# WR_OSC.net
KiCad netlist of a schematic drawn in Altium Designer
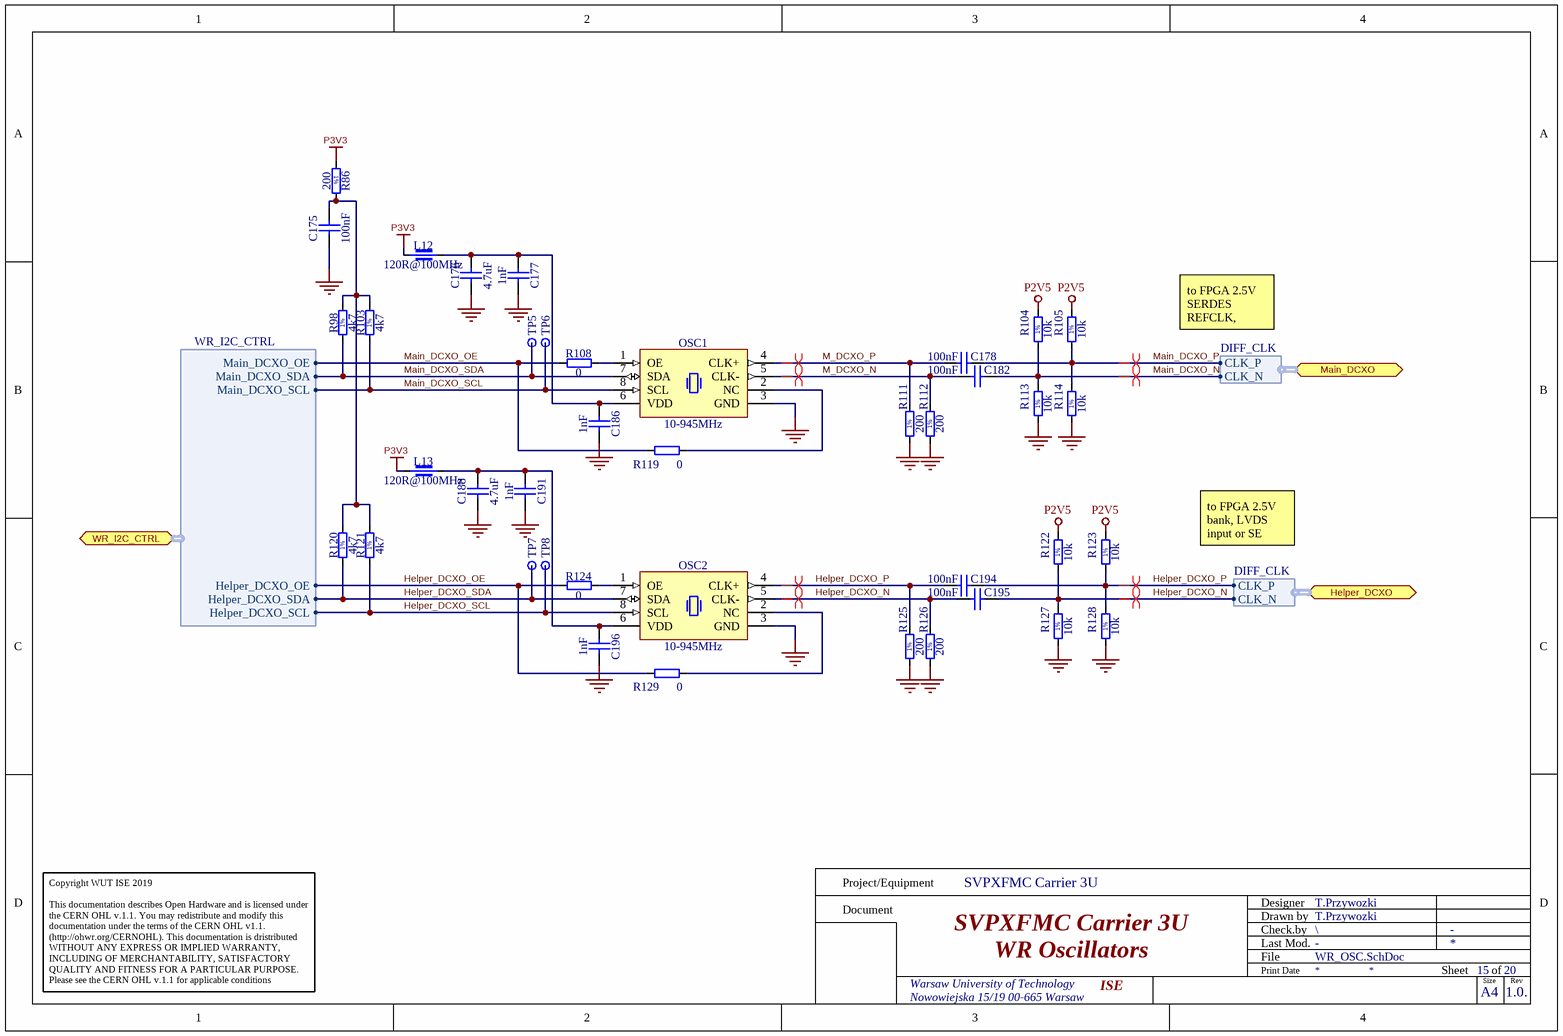
[diagram p0: WR_OSC.SchDoc]

(export (version "E")
  (design (tool "Eeschema 10.0.6"))
  (components
    (comp (ref "C175")
      (value "100nF")
      (footprint "CAPC0603X33N")
      (description "Non-polarised capacitor")
      (fields
        (field (name "MANUFACTURER PART NUMBER") "CC0201_100NF_6.3V_10%_X5R")
        (field (name "MANUFACTURER") "GENERIC")
        (field (name "AUTHOR") "CERN DEM JLC")
      )
      (libsource (lib "Capacitors") (part "Capacitor - non polarized"))
    )
    (comp (ref "C176")
      (value "4.7uF")
      (footprint "CAPC1608X90N")
      (description "Non-polarised capacitor")
      (fields
        (field (name "MANUFACTURER PART NUMBER") "CC0603_4.7UF_25V_10%_X5R")
        (field (name "MANUFACTURER") "GENERIC")
        (field (name "AUTHOR") "CERN DEM JLC")
      )
      (libsource (lib "Capacitors") (part "Capacitor - non polarized"))
    )
    (comp (ref "C177")
      (value "1nF")
      (footprint "CAPC0603X33N")
      (description "Non-polarised capacitor")
      (fields
        (field (name "MANUFACTURER PART NUMBER") "CC0201_1NF_16V_10%_X5R")
        (field (name "MANUFACTURER") "GENERIC")
        (field (name "AUTHOR") "CERN DEM JLC")
      )
      (libsource (lib "Capacitors") (part "Capacitor - non polarized"))
    )
    (comp (ref "C178")
      (value "100nF")
      (footprint "CAPC1005X55N")
      (description "Non-polarised capacitor")
      (fields
        (field (name "MANUFACTURER PART NUMBER") "CC0402_100NF_16V_10%_X5R")
        (field (name "MANUFACTURER") "GENERIC")
        (field (name "AUTHOR") "CERN DEM JLC")
      )
      (libsource (lib "Capacitors") (part "Capacitor - non polarized"))
    )
    (comp (ref "C182")
      (value "100nF")
      (footprint "CAPC1005X55N")
      (description "Non-polarised capacitor")
      (fields
        (field (name "MANUFACTURER PART NUMBER") "CC0402_100NF_16V_10%_X5R")
        (field (name "MANUFACTURER") "GENERIC")
        (field (name "AUTHOR") "CERN DEM JLC")
      )
      (libsource (lib "Capacitors") (part "Capacitor - non polarized"))
    )
    (comp (ref "C186")
      (value "1nF")
      (footprint "CAPC0603X33N")
      (description "Non-polarised capacitor")
      (fields
        (field (name "MANUFACTURER PART NUMBER") "CC0201_1NF_16V_10%_X5R")
        (field (name "MANUFACTURER") "GENERIC")
        (field (name "AUTHOR") "CERN DEM JLC")
      )
      (libsource (lib "Capacitors") (part "Capacitor - non polarized"))
    )
    (comp (ref "C188")
      (value "4.7uF")
      (footprint "CAPC1608X90N")
      (description "Non-polarised capacitor")
      (fields
        (field (name "MANUFACTURER PART NUMBER") "CC0603_4.7UF_25V_10%_X5R")
        (field (name "MANUFACTURER") "GENERIC")
        (field (name "AUTHOR") "CERN DEM JLC")
      )
      (libsource (lib "Capacitors") (part "Capacitor - non polarized"))
    )
    (comp (ref "C191")
      (value "1nF")
      (footprint "CAPC0603X33N")
      (description "Non-polarised capacitor")
      (fields
        (field (name "MANUFACTURER PART NUMBER") "CC0201_1NF_16V_10%_X5R")
        (field (name "MANUFACTURER") "GENERIC")
        (field (name "AUTHOR") "CERN DEM JLC")
      )
      (libsource (lib "Capacitors") (part "Capacitor - non polarized"))
    )
    (comp (ref "C194")
      (value "100nF")
      (footprint "CAPC1005X55N")
      (description "Non-polarised capacitor")
      (fields
        (field (name "MANUFACTURER PART NUMBER") "CC0402_100NF_16V_10%_X5R")
        (field (name "MANUFACTURER") "GENERIC")
        (field (name "AUTHOR") "CERN DEM JLC")
      )
      (libsource (lib "Capacitors") (part "Capacitor - non polarized"))
    )
    (comp (ref "C195")
      (value "100nF")
      (footprint "CAPC1005X55N")
      (description "Non-polarised capacitor")
      (fields
        (field (name "MANUFACTURER PART NUMBER") "CC0402_100NF_16V_10%_X5R")
        (field (name "MANUFACTURER") "GENERIC")
        (field (name "AUTHOR") "CERN DEM JLC")
      )
      (libsource (lib "Capacitors") (part "Capacitor - non polarized"))
    )
    (comp (ref "C196")
      (value "1nF")
      (footprint "CAPC0603X33N")
      (description "Non-polarised capacitor")
      (fields
        (field (name "MANUFACTURER PART NUMBER") "CC0201_1NF_16V_10%_X5R")
        (field (name "MANUFACTURER") "GENERIC")
        (field (name "AUTHOR") "CERN DEM JLC")
      )
      (libsource (lib "Capacitors") (part "Capacitor - non polarized"))
    )
    (comp (ref "L12")
      (value "120R@100MHz")
      (footprint "INDC1608X95N")
      (fields
        (field (name "MANUFACTURER PART NUMBER") "BLM18PG121SN1D")
        (field (name "MANUFACTURER") "MURATA")
        (field (name "PART NUMBER") "IND0603_MURATA_BLM18PG121SN1D")
        (field (name "AUTHOR") "CERN DEM BC")
      )
      (libsource (lib "Inductors & Transformers") (part "Ferrite Bead"))
    )
    (comp (ref "L13")
      (value "120R@100MHz")
      (footprint "INDC1608X95N")
      (fields
        (field (name "MANUFACTURER PART NUMBER") "BLM18PG121SN1D")
        (field (name "MANUFACTURER") "MURATA")
        (field (name "PART NUMBER") "IND0603_MURATA_BLM18PG121SN1D")
        (field (name "AUTHOR") "CERN DEM BC")
      )
      (libsource (lib "Inductors & Transformers") (part "Ferrite Bead"))
    )
    (comp (ref "OSC1")
      (value "10-945MHz")
      (footprint "OSC_SILICON-LAB_SI570")
      (description "Ultra Low Jitter I2C Programmable XO (95 fs), 0.2 to 250MHz")
      (fields
        (field (name "MANUFACTURER") "Silabs")
        (field (name "MANUFACTURER PART NUMBER") "570ACA001527DGR")
      )
      (libsource (lib "TP_LIB") (part "570ACA001527DGR"))
    )
    (comp (ref "OSC2")
      (value "10-945MHz")
      (footprint "OSC_SILICON-LAB_SI570")
      (description "Ultra Low Jitter I2C Programmable XO (95 fs), 0.2 to 250MHz")
      (fields
        (field (name "MANUFACTURER") "Silabs")
        (field (name "MANUFACTURER PART NUMBER") "570ACA001527DGR")
      )
      (libsource (lib "TP_LIB") (part "570ACA001527DGR"))
    )
    (comp (ref "R86")
      (value "200")
      (footprint "RESC1005X40N")
      (description "Resistor - 1%")
      (fields
        (field (name "MANUFACTURER PART NUMBER") "R0402_200R_1%_0.0625W_100PPM")
        (field (name "MANUFACTURER") "GENERIC")
        (field (name "AUTHOR") "CERN DEM JLC")
      )
      (libsource (lib "Resistors") (part "Resistor - 1%"))
    )
    (comp (ref "R98")
      (value "4k7")
      (footprint "RESC1005X40N")
      (description "Resistor - 1%")
      (fields
        (field (name "MANUFACTURER PART NUMBER") "R0402_4K7_1%_0.0625W_100PPM")
        (field (name "MANUFACTURER") "GENERIC")
        (field (name "AUTHOR") "CERN DEM JLC")
      )
      (libsource (lib "Resistors") (part "Resistor - 1%"))
    )
    (comp (ref "R103")
      (value "4k7")
      (footprint "RESC1005X40N")
      (description "Resistor - 1%")
      (fields
        (field (name "MANUFACTURER PART NUMBER") "R0402_4K7_1%_0.0625W_100PPM")
        (field (name "MANUFACTURER") "GENERIC")
        (field (name "AUTHOR") "CERN DEM JLC")
      )
      (libsource (lib "Resistors") (part "Resistor - 1%"))
    )
    (comp (ref "R104")
      (value "10k")
      (footprint "RESC1005X40N")
      (description "Resistor - 1%")
      (fields
        (field (name "MANUFACTURER PART NUMBER") "R0402_10K_1%_0.0625W_100PPM")
        (field (name "MANUFACTURER") "GENERIC")
        (field (name "AUTHOR") "CERN DEM JLC")
      )
      (libsource (lib "Resistors") (part "Resistor - 1%"))
    )
    (comp (ref "R105")
      (value "10k")
      (footprint "RESC1005X40N")
      (description "Resistor - 1%")
      (fields
        (field (name "MANUFACTURER PART NUMBER") "R0402_10K_1%_0.0625W_100PPM")
        (field (name "MANUFACTURER") "GENERIC")
        (field (name "AUTHOR") "CERN DEM JLC")
      )
      (libsource (lib "Resistors") (part "Resistor - 1%"))
    )
    (comp (ref "R108")
      (value "0")
      (footprint "RESC1005X40N")
      (description "Resistor")
      (fields
        (field (name "MANUFACTURER PART NUMBER") "R0402_0R_JUMPER")
        (field (name "MANUFACTURER") "GENERIC")
        (field (name "AUTHOR") "CERN DEM JLC")
      )
      (libsource (lib "Resistors") (part "Resistor"))
    )
    (comp (ref "R111")
      (value "200")
      (footprint "RESC1005X40N")
      (description "Resistor - 1%")
      (fields
        (field (name "MANUFACTURER PART NUMBER") "R0402_200R_1%_0.0625W_100PPM")
        (field (name "MANUFACTURER") "GENERIC")
        (field (name "AUTHOR") "CERN DEM JLC")
      )
      (libsource (lib "Resistors") (part "Resistor - 1%"))
    )
    (comp (ref "R112")
      (value "200")
      (footprint "RESC1005X40N")
      (description "Resistor - 1%")
      (fields
        (field (name "MANUFACTURER PART NUMBER") "R0402_200R_1%_0.0625W_100PPM")
        (field (name "MANUFACTURER") "GENERIC")
        (field (name "AUTHOR") "CERN DEM JLC")
      )
      (libsource (lib "Resistors") (part "Resistor - 1%"))
    )
    (comp (ref "R113")
      (value "10k")
      (footprint "RESC1005X40N")
      (description "Resistor - 1%")
      (fields
        (field (name "MANUFACTURER PART NUMBER") "R0402_10K_1%_0.0625W_100PPM")
        (field (name "MANUFACTURER") "GENERIC")
        (field (name "AUTHOR") "CERN DEM JLC")
      )
      (libsource (lib "Resistors") (part "Resistor - 1%"))
    )
    (comp (ref "R114")
      (value "10k")
      (footprint "RESC1005X40N")
      (description "Resistor - 1%")
      (fields
        (field (name "MANUFACTURER PART NUMBER") "R0402_10K_1%_0.0625W_100PPM")
        (field (name "MANUFACTURER") "GENERIC")
        (field (name "AUTHOR") "CERN DEM JLC")
      )
      (libsource (lib "Resistors") (part "Resistor - 1%"))
    )
    (comp (ref "R119")
      (value "0")
      (footprint "RESC1005X40N")
      (description "Resistor")
      (fields
        (field (name "MANUFACTURER PART NUMBER") "R0402_0R_JUMPER")
        (field (name "MANUFACTURER") "GENERIC")
        (field (name "AUTHOR") "CERN DEM JLC")
      )
      (libsource (lib "Resistors") (part "Resistor"))
    )
    (comp (ref "R120")
      (value "4k7")
      (footprint "RESC1005X40N")
      (description "Resistor - 1%")
      (fields
        (field (name "MANUFACTURER PART NUMBER") "R0402_4K7_1%_0.0625W_100PPM")
        (field (name "MANUFACTURER") "GENERIC")
        (field (name "AUTHOR") "CERN DEM JLC")
      )
      (libsource (lib "Resistors") (part "Resistor - 1%"))
    )
    (comp (ref "R121")
      (value "4k7")
      (footprint "RESC1005X40N")
      (description "Resistor - 1%")
      (fields
        (field (name "MANUFACTURER PART NUMBER") "R0402_4K7_1%_0.0625W_100PPM")
        (field (name "MANUFACTURER") "GENERIC")
        (field (name "AUTHOR") "CERN DEM JLC")
      )
      (libsource (lib "Resistors") (part "Resistor - 1%"))
    )
    (comp (ref "R122")
      (value "10k")
      (footprint "RESC1005X40N")
      (description "Resistor - 1%")
      (fields
        (field (name "MANUFACTURER PART NUMBER") "R0402_10K_1%_0.0625W_100PPM")
        (field (name "MANUFACTURER") "GENERIC")
        (field (name "AUTHOR") "CERN DEM JLC")
      )
      (libsource (lib "Resistors") (part "Resistor - 1%"))
    )
    (comp (ref "R123")
      (value "10k")
      (footprint "RESC1005X40N")
      (description "Resistor - 1%")
      (fields
        (field (name "MANUFACTURER PART NUMBER") "R0402_10K_1%_0.0625W_100PPM")
        (field (name "MANUFACTURER") "GENERIC")
        (field (name "AUTHOR") "CERN DEM JLC")
      )
      (libsource (lib "Resistors") (part "Resistor - 1%"))
    )
    (comp (ref "R124")
      (value "0")
      (footprint "RESC1005X40N")
      (description "Resistor")
      (fields
        (field (name "MANUFACTURER PART NUMBER") "R0402_0R_JUMPER")
        (field (name "MANUFACTURER") "GENERIC")
        (field (name "AUTHOR") "CERN DEM JLC")
      )
      (libsource (lib "Resistors") (part "Resistor"))
    )
    (comp (ref "R125")
      (value "200")
      (footprint "RESC1005X40N")
      (description "Resistor - 1%")
      (fields
        (field (name "MANUFACTURER PART NUMBER") "R0402_200R_1%_0.0625W_100PPM")
        (field (name "MANUFACTURER") "GENERIC")
        (field (name "AUTHOR") "CERN DEM JLC")
      )
      (libsource (lib "Resistors") (part "Resistor - 1%"))
    )
    (comp (ref "R126")
      (value "200")
      (footprint "RESC1005X40N")
      (description "Resistor - 1%")
      (fields
        (field (name "MANUFACTURER PART NUMBER") "R0402_200R_1%_0.0625W_100PPM")
        (field (name "MANUFACTURER") "GENERIC")
        (field (name "AUTHOR") "CERN DEM JLC")
      )
      (libsource (lib "Resistors") (part "Resistor - 1%"))
    )
    (comp (ref "R127")
      (value "10k")
      (footprint "RESC1005X40N")
      (description "Resistor - 1%")
      (fields
        (field (name "MANUFACTURER PART NUMBER") "R0402_10K_1%_0.0625W_100PPM")
        (field (name "MANUFACTURER") "GENERIC")
        (field (name "AUTHOR") "CERN DEM JLC")
      )
      (libsource (lib "Resistors") (part "Resistor - 1%"))
    )
    (comp (ref "R128")
      (value "10k")
      (footprint "RESC1005X40N")
      (description "Resistor - 1%")
      (fields
        (field (name "MANUFACTURER PART NUMBER") "R0402_10K_1%_0.0625W_100PPM")
        (field (name "MANUFACTURER") "GENERIC")
        (field (name "AUTHOR") "CERN DEM JLC")
      )
      (libsource (lib "Resistors") (part "Resistor - 1%"))
    )
    (comp (ref "R129")
      (value "0")
      (footprint "RESC1005X40N")
      (description "Resistor")
      (fields
        (field (name "MANUFACTURER PART NUMBER") "R0402_0R_JUMPER")
        (field (name "MANUFACTURER") "GENERIC")
        (field (name "AUTHOR") "CERN DEM JLC")
      )
      (libsource (lib "Resistors") (part "Resistor"))
    )
    (comp (ref "TP5")
      (value "Test Point")
      (footprint "TPS127")
      (fields (field (name "PART NUMBER") "SMD_PAD_1.27X1.27MM") (field (name "AUTHOR") "CERN DEM JLC"))
      (libsource (lib "Eletro-mechanical") (part "Test Point"))
    )
    (comp (ref "TP6")
      (value "Test Point")
      (footprint "TPS127")
      (fields (field (name "PART NUMBER") "SMD_PAD_1.27X1.27MM") (field (name "AUTHOR") "CERN DEM JLC"))
      (libsource (lib "Eletro-mechanical") (part "Test Point"))
    )
    (comp (ref "TP7")
      (value "Test Point")
      (footprint "TPS127")
      (fields (field (name "PART NUMBER") "SMD_PAD_1.27X1.27MM") (field (name "AUTHOR") "CERN DEM JLC"))
      (libsource (lib "Eletro-mechanical") (part "Test Point"))
    )
    (comp (ref "TP8")
      (value "Test Point")
      (footprint "TPS127")
      (fields (field (name "PART NUMBER") "SMD_PAD_1.27X1.27MM") (field (name "AUTHOR") "CERN DEM JLC"))
      (libsource (lib "Eletro-mechanical") (part "Test Point"))
    )
  )
  (nets
    (net (code "3") (name "/Helper_DCXO_N") (class "Default")
      (node (ref "C195") (pin "1") (pinfunction "1_1") (pintype "passive"))
      (node (ref "C195") (pin "2") (pinfunction "2_2") (pintype "passive"))
      (node (ref "OSC2") (pin "5") (pinfunction "CLK-_5") (pintype "output"))
      (node (ref "R122") (pin "1") (pinfunction "1_1") (pintype "passive"))
      (node (ref "R126") (pin "2") (pinfunction "2_2") (pintype "passive"))
      (node (ref "R127") (pin "2") (pinfunction "2_2") (pintype "passive"))
    )
    (net (code "4") (name "/Helper_DCXO_OE") (class "Default")
      (node (ref "R124") (pin "1") (pinfunction "1_1") (pintype "passive"))
      (node (ref "R129") (pin "1") (pinfunction "1_1") (pintype "passive"))
    )
    (net (code "5") (name "/Helper_DCXO_P") (class "Default")
      (node (ref "C194") (pin "1") (pinfunction "1_1") (pintype "passive"))
      (node (ref "C194") (pin "2") (pinfunction "2_2") (pintype "passive"))
      (node (ref "OSC2") (pin "4") (pinfunction "CLK+_4") (pintype "output"))
      (node (ref "R123") (pin "1") (pinfunction "1_1") (pintype "passive"))
      (node (ref "R125") (pin "2") (pinfunction "2_2") (pintype "passive"))
      (node (ref "R128") (pin "2") (pinfunction "2_2") (pintype "passive"))
    )
    (net (code "6") (name "/Helper_DCXO_SCL") (class "Default")
      (node (ref "OSC2") (pin "8") (pinfunction "SCL_8") (pintype "input"))
      (node (ref "R121") (pin "1") (pinfunction "1_1") (pintype "passive"))
      (node (ref "TP8") (pin "1") (pinfunction "1_1") (pintype "bidirectional"))
    )
    (net (code "7") (name "/Helper_DCXO_SDA") (class "Default")
      (node (ref "OSC2") (pin "7") (pinfunction "SDA_7") (pintype "bidirectional"))
      (node (ref "R120") (pin "1") (pinfunction "1_1") (pintype "passive"))
      (node (ref "TP7") (pin "1") (pinfunction "1_1") (pintype "bidirectional"))
    )
    (net (code "8") (name "/M_DCXO_N") (class "Default")
      (node (ref "C182") (pin "1") (pinfunction "1_1") (pintype "passive"))
      (node (ref "OSC1") (pin "5") (pinfunction "CLK-_5") (pintype "output"))
      (node (ref "R112") (pin "2") (pinfunction "2_2") (pintype "passive"))
    )
    (net (code "9") (name "/M_DCXO_P") (class "Default")
      (node (ref "C178") (pin "1") (pinfunction "1_1") (pintype "passive"))
      (node (ref "OSC1") (pin "4") (pinfunction "CLK+_4") (pintype "output"))
      (node (ref "R111") (pin "2") (pinfunction "2_2") (pintype "passive"))
    )
    (net (code "10") (name "/Main_DCXO_N") (class "Default")
      (node (ref "C182") (pin "2") (pinfunction "2_2") (pintype "passive"))
      (node (ref "R104") (pin "1") (pinfunction "1_1") (pintype "passive"))
      (node (ref "R113") (pin "2") (pinfunction "2_2") (pintype "passive"))
    )
    (net (code "11") (name "/Main_DCXO_OE") (class "Default")
      (node (ref "R108") (pin "1") (pinfunction "1_1") (pintype "passive"))
      (node (ref "R119") (pin "1") (pinfunction "1_1") (pintype "passive"))
    )
    (net (code "12") (name "/Main_DCXO_P") (class "Default")
      (node (ref "C178") (pin "2") (pinfunction "2_2") (pintype "passive"))
      (node (ref "R105") (pin "1") (pinfunction "1_1") (pintype "passive"))
      (node (ref "R114") (pin "2") (pinfunction "2_2") (pintype "passive"))
    )
    (net (code "13") (name "/Main_DCXO_SCL") (class "Default")
      (node (ref "OSC1") (pin "8") (pinfunction "SCL_8") (pintype "input"))
      (node (ref "R103") (pin "1") (pinfunction "1_1") (pintype "passive"))
      (node (ref "TP6") (pin "1") (pinfunction "1_1") (pintype "bidirectional"))
    )
    (net (code "14") (name "/Main_DCXO_SDA") (class "Default")
      (node (ref "OSC1") (pin "7") (pinfunction "SDA_7") (pintype "bidirectional"))
      (node (ref "R98") (pin "1") (pinfunction "1_1") (pintype "passive"))
      (node (ref "TP5") (pin "1") (pinfunction "1_1") (pintype "bidirectional"))
    )
    (net (code "17") (name "GND") (class "Default")
      (node (ref "C175") (pin "1") (pinfunction "1_1") (pintype "passive"))
      (node (ref "C176") (pin "1") (pinfunction "1_1") (pintype "passive"))
      (node (ref "C177") (pin "1") (pinfunction "1_1") (pintype "passive"))
      (node (ref "C186") (pin "1") (pinfunction "1_1") (pintype "passive"))
      (node (ref "C188") (pin "1") (pinfunction "1_1") (pintype "passive"))
      (node (ref "C191") (pin "1") (pinfunction "1_1") (pintype "passive"))
      (node (ref "C196") (pin "1") (pinfunction "1_1") (pintype "passive"))
      (node (ref "OSC1") (pin "3") (pinfunction "GND_3") (pintype "power_in"))
      (node (ref "OSC2") (pin "3") (pinfunction "GND_3") (pintype "power_in"))
      (node (ref "R111") (pin "1") (pinfunction "1_1") (pintype "passive"))
      (node (ref "R112") (pin "1") (pinfunction "1_1") (pintype "passive"))
      (node (ref "R113") (pin "1") (pinfunction "1_1") (pintype "passive"))
      (node (ref "R114") (pin "1") (pinfunction "1_1") (pintype "passive"))
      (node (ref "R125") (pin "1") (pinfunction "1_1") (pintype "passive"))
      (node (ref "R126") (pin "1") (pinfunction "1_1") (pintype "passive"))
      (node (ref "R127") (pin "1") (pinfunction "1_1") (pintype "passive"))
      (node (ref "R128") (pin "1") (pinfunction "1_1") (pintype "passive"))
    )
    (net (code "18") (name "Net-(C175-Pad2)") (class "Default")
      (node (ref "C175") (pin "2") (pinfunction "2_2") (pintype "passive"))
      (node (ref "R103") (pin "2") (pinfunction "2_2") (pintype "passive"))
      (node (ref "R120") (pin "2") (pinfunction "2_2") (pintype "passive"))
      (node (ref "R121") (pin "2") (pinfunction "2_2") (pintype "passive"))
      (node (ref "R86") (pin "2") (pinfunction "2_2") (pintype "passive"))
      (node (ref "R98") (pin "2") (pinfunction "2_2") (pintype "passive"))
    )
    (net (code "19") (name "Net-(OSC1-NC)") (class "Default")
      (node (ref "OSC1") (pin "2") (pinfunction "NC_2") (pintype "passive"))
      (node (ref "R119") (pin "2") (pinfunction "2_2") (pintype "passive"))
    )
    (net (code "20") (name "Net-(OSC1-OE)") (class "Default")
      (node (ref "OSC1") (pin "1") (pinfunction "OE_1") (pintype "input"))
      (node (ref "R108") (pin "2") (pinfunction "2_2") (pintype "passive"))
    )
    (net (code "21") (name "Net-(OSC1-VDD)") (class "Default")
      (node (ref "C176") (pin "2") (pinfunction "2_2") (pintype "passive"))
      (node (ref "C177") (pin "2") (pinfunction "2_2") (pintype "passive"))
      (node (ref "C186") (pin "2") (pinfunction "2_2") (pintype "passive"))
      (node (ref "L12") (pin "2") (pinfunction "2_2") (pintype "passive"))
      (node (ref "OSC1") (pin "6") (pinfunction "VDD_6") (pintype "power_in"))
    )
    (net (code "22") (name "Net-(OSC2-NC)") (class "Default")
      (node (ref "OSC2") (pin "2") (pinfunction "NC_2") (pintype "passive"))
      (node (ref "R129") (pin "2") (pinfunction "2_2") (pintype "passive"))
    )
    (net (code "23") (name "Net-(OSC2-OE)") (class "Default")
      (node (ref "OSC2") (pin "1") (pinfunction "OE_1") (pintype "input"))
      (node (ref "R124") (pin "2") (pinfunction "2_2") (pintype "passive"))
    )
    (net (code "24") (name "Net-(OSC2-VDD)") (class "Default")
      (node (ref "C188") (pin "2") (pinfunction "2_2") (pintype "passive"))
      (node (ref "C191") (pin "2") (pinfunction "2_2") (pintype "passive"))
      (node (ref "C196") (pin "2") (pinfunction "2_2") (pintype "passive"))
      (node (ref "L13") (pin "2") (pinfunction "2_2") (pintype "passive"))
      (node (ref "OSC2") (pin "6") (pinfunction "VDD_6") (pintype "power_in"))
    )
    (net (code "25") (name "P2V5") (class "Default")
      (node (ref "R104") (pin "2") (pinfunction "2_2") (pintype "passive"))
      (node (ref "R105") (pin "2") (pinfunction "2_2") (pintype "passive"))
      (node (ref "R122") (pin "2") (pinfunction "2_2") (pintype "passive"))
      (node (ref "R123") (pin "2") (pinfunction "2_2") (pintype "passive"))
    )
    (net (code "26") (name "P3V3") (class "Default")
      (node (ref "L12") (pin "1") (pinfunction "1_1") (pintype "passive"))
      (node (ref "L13") (pin "1") (pinfunction "1_1") (pintype "passive"))
      (node (ref "R86") (pin "1") (pinfunction "1_1") (pintype "passive"))
    )
  )
)
